# Clock_circuit.net
KiCad netlist of a schematic drawn in Altium Designer
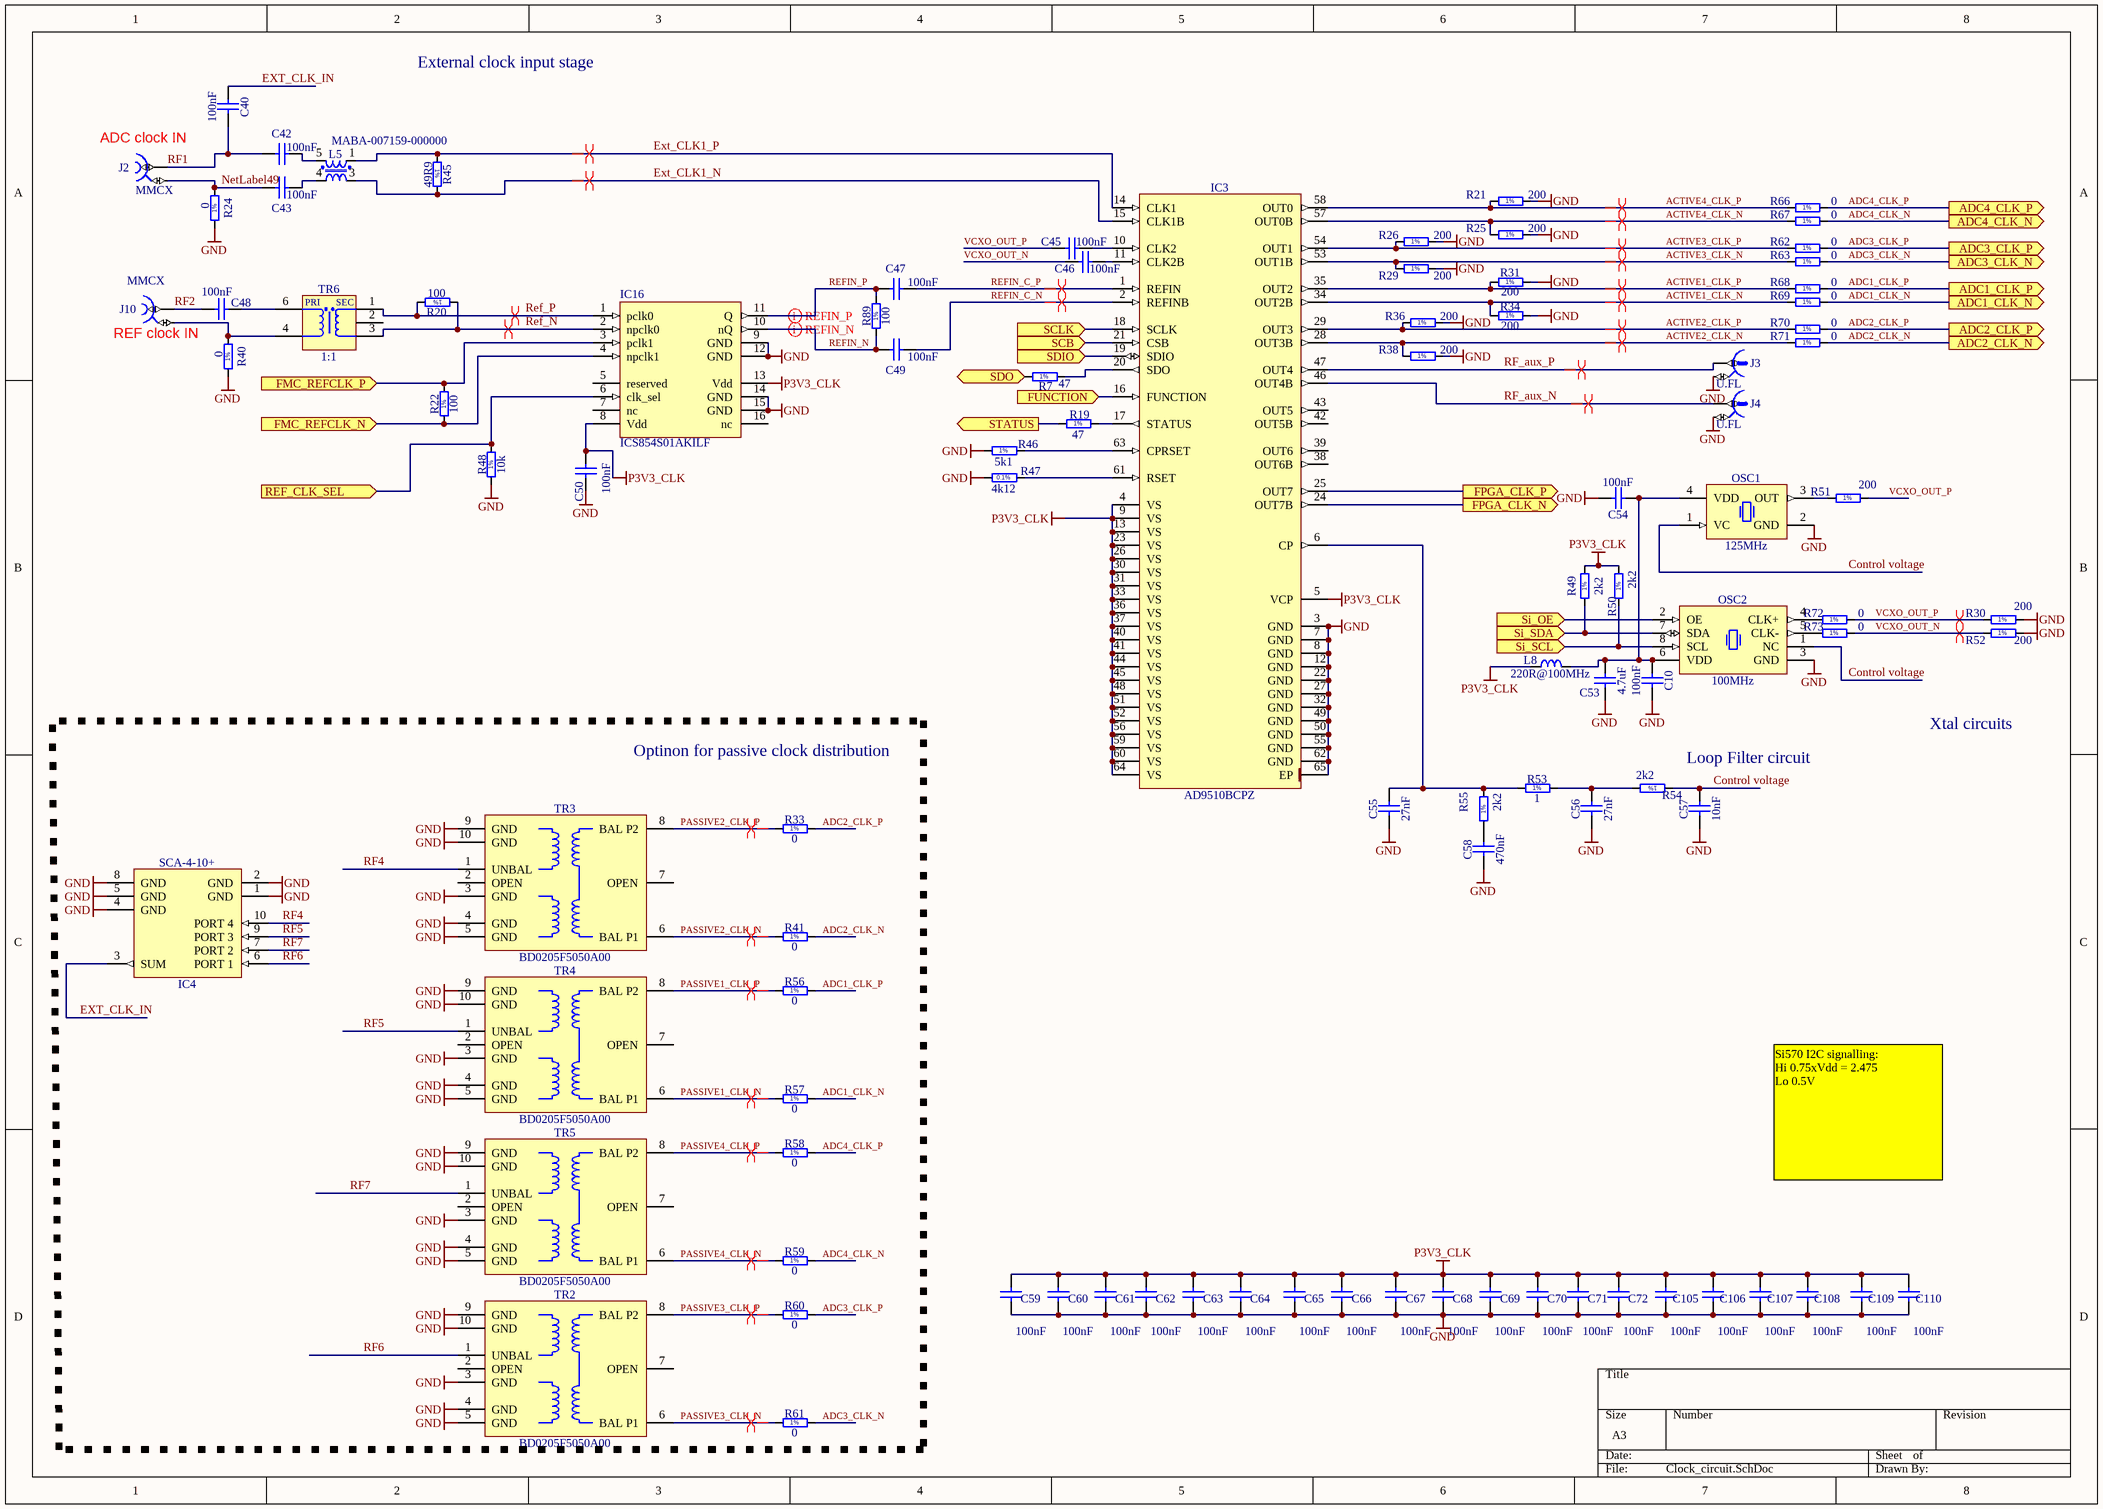
[diagram p0: Clock_circuit.SchDoc]

(export (version "E")
  (design (tool "Eeschema 10.0.6"))
  (components
    (comp (ref "C10")
      (value "100nF")
      (footprint "CAPC0603X33N")
      (description "Non-polarised capacitor")
      (fields
        (field (name "PART NUMBER") "CC0201_100NF_6.3V_10%_X5R")
        (field (name "VOLTAGE") "6.3V")
        (field (name "AUTHOR") "CERN DEM JLC")
      )
      (libsource (lib "Capacitors") (part "Capacitor - non polarized"))
    )
    (comp (ref "C40")
      (value "100nF")
      (footprint "CAPC0603X33N")
      (description "Non-polarised capacitor")
      (fields
        (field (name "PART NUMBER") "CC0201_100NF_6.3V_10%_X5R")
        (field (name "VOLTAGE") "6.3V")
        (field (name "AUTHOR") "CERN DEM JLC")
      )
      (libsource (lib "Capacitors") (part "Capacitor - non polarized"))
    )
    (comp (ref "C42")
      (value "100nF")
      (footprint "CAPC0603X33N")
      (description "Non-polarised capacitor")
      (fields
        (field (name "PART NUMBER") "CC0201_100NF_6.3V_10%_X5R")
        (field (name "VOLTAGE") "6.3V")
        (field (name "AUTHOR") "CERN DEM JLC")
      )
      (libsource (lib "Capacitors") (part "Capacitor - non polarized"))
    )
    (comp (ref "C43")
      (value "100nF")
      (footprint "CAPC0603X33N")
      (description "Non-polarised capacitor")
      (fields
        (field (name "PART NUMBER") "CC0201_100NF_6.3V_10%_X5R")
        (field (name "VOLTAGE") "6.3V")
        (field (name "AUTHOR") "CERN DEM JLC")
      )
      (libsource (lib "Capacitors") (part "Capacitor - non polarized"))
    )
    (comp (ref "C45")
      (value "100nF")
      (footprint "CAPC0603X33N")
      (description "Non-polarised capacitor")
      (fields
        (field (name "PART NUMBER") "CC0201_100NF_6.3V_10%_X5R")
        (field (name "VOLTAGE") "6.3V")
        (field (name "AUTHOR") "CERN DEM JLC")
      )
      (libsource (lib "Capacitors") (part "Capacitor - non polarized"))
    )
    (comp (ref "C46")
      (value "100nF")
      (footprint "CAPC0603X33N")
      (description "Non-polarised capacitor")
      (fields
        (field (name "PART NUMBER") "CC0201_100NF_6.3V_10%_X5R")
        (field (name "VOLTAGE") "6.3V")
        (field (name "AUTHOR") "CERN DEM JLC")
      )
      (libsource (lib "Capacitors") (part "Capacitor - non polarized"))
    )
    (comp (ref "C47")
      (value "100nF")
      (footprint "CAPC0603X33N")
      (description "Non-polarised capacitor")
      (fields
        (field (name "PART NUMBER") "CC0201_100NF_6.3V_10%_X5R")
        (field (name "VOLTAGE") "6.3V")
        (field (name "AUTHOR") "CERN DEM JLC")
      )
      (libsource (lib "Capacitors") (part "Capacitor - non polarized"))
    )
    (comp (ref "C48")
      (value "100nF")
      (footprint "CAPC0603X33N")
      (description "Non-polarised capacitor")
      (fields
        (field (name "PART NUMBER") "CC0201_100NF_6.3V_10%_X5R")
        (field (name "VOLTAGE") "6.3V")
        (field (name "AUTHOR") "CERN DEM JLC")
      )
      (libsource (lib "Capacitors") (part "Capacitor - non polarized"))
    )
    (comp (ref "C49")
      (value "100nF")
      (footprint "CAPC0603X33N")
      (description "Non-polarised capacitor")
      (fields
        (field (name "PART NUMBER") "CC0201_100NF_6.3V_10%_X5R")
        (field (name "VOLTAGE") "6.3V")
        (field (name "AUTHOR") "CERN DEM JLC")
      )
      (libsource (lib "Capacitors") (part "Capacitor - non polarized"))
    )
    (comp (ref "C50")
      (value "100nF")
      (footprint "CAPC0603X33N")
      (description "Non-polarised capacitor")
      (fields
        (field (name "PART NUMBER") "CC0201_100NF_6.3V_10%_X5R")
        (field (name "VOLTAGE") "6.3V")
        (field (name "AUTHOR") "CERN DEM JLC")
      )
      (libsource (lib "Capacitors") (part "Capacitor - non polarized"))
    )
    (comp (ref "C53")
      (value "4.7uF")
      (footprint "CAPC1608X87N")
      (description "Non-polarised capacitor")
      (fields
        (field (name "PART NUMBER") "CC0603_4.7UF_6.3V_10%_X5R")
        (field (name "VOLTAGE") "6.3V")
        (field (name "AUTHOR") "CERN DEM JLC")
      )
      (libsource (lib "Capacitors") (part "Capacitor - non polarized"))
    )
    (comp (ref "C54")
      (value "100nF")
      (footprint "CAPC0603X33N")
      (description "Non-polarised capacitor")
      (fields
        (field (name "PART NUMBER") "CC0201_100NF_6.3V_10%_X5R")
        (field (name "VOLTAGE") "6.3V")
        (field (name "AUTHOR") "CERN DEM JLC")
      )
      (libsource (lib "Capacitors") (part "Capacitor - non polarized"))
    )
    (comp (ref "C55")
      (value "27nF")
      (footprint "CAPC1608X87N")
      (description "Non-polarised capacitor")
      (fields
        (field (name "PART NUMBER") "CC0603_27NF_25V_10%_X7R")
        (field (name "VOLTAGE") "25V")
        (field (name "AUTHOR") "CERN DEM JLC")
      )
      (libsource (lib "Capacitors") (part "Capacitor - non polarized"))
    )
    (comp (ref "C56")
      (value "27nF")
      (footprint "CAPC1608X87N")
      (description "Non-polarised capacitor")
      (fields
        (field (name "PART NUMBER") "CC0603_27NF_25V_10%_X7R")
        (field (name "VOLTAGE") "25V")
        (field (name "AUTHOR") "CERN DEM JLC")
      )
      (libsource (lib "Capacitors") (part "Capacitor - non polarized"))
    )
    (comp (ref "C57")
      (value "10nF")
      (footprint "CAPC1608X87N")
      (description "Non-polarised capacitor")
      (fields
        (field (name "PART NUMBER") "CC0603_10NF_50V_10%_X7R")
        (field (name "VOLTAGE") "50V")
        (field (name "AUTHOR") "CERN DEM JLC")
      )
      (libsource (lib "Capacitors") (part "Capacitor - non polarized"))
    )
    (comp (ref "C58")
      (value "470nF")
      (footprint "CAPC1608X87N")
      (description "Non-polarised capacitor")
      (fields
        (field (name "PART NUMBER") "CC0603_470NF_16V_10%_X5R")
        (field (name "VOLTAGE") "16V")
        (field (name "AUTHOR") "CERN DEM JLC")
      )
      (libsource (lib "Capacitors") (part "Capacitor - non polarized"))
    )
    (comp (ref "C59")
      (value "100nF")
      (footprint "CAPC0603X33N")
      (description "Non-polarised capacitor")
      (fields
        (field (name "PART NUMBER") "CC0201_100NF_6.3V_10%_X5R")
        (field (name "VOLTAGE") "6.3V")
        (field (name "AUTHOR") "CERN DEM JLC")
      )
      (libsource (lib "Capacitors") (part "Capacitor - non polarized"))
    )
    (comp (ref "C60")
      (value "100nF")
      (footprint "CAPC0603X33N")
      (description "Non-polarised capacitor")
      (fields
        (field (name "PART NUMBER") "CC0201_100NF_6.3V_10%_X5R")
        (field (name "VOLTAGE") "6.3V")
        (field (name "AUTHOR") "CERN DEM JLC")
      )
      (libsource (lib "Capacitors") (part "Capacitor - non polarized"))
    )
    (comp (ref "C61")
      (value "100nF")
      (footprint "CAPC0603X33N")
      (description "Non-polarised capacitor")
      (fields
        (field (name "PART NUMBER") "CC0201_100NF_6.3V_10%_X5R")
        (field (name "VOLTAGE") "6.3V")
        (field (name "AUTHOR") "CERN DEM JLC")
      )
      (libsource (lib "Capacitors") (part "Capacitor - non polarized"))
    )
    (comp (ref "C62")
      (value "100nF")
      (footprint "CAPC0603X33N")
      (description "Non-polarised capacitor")
      (fields
        (field (name "PART NUMBER") "CC0201_100NF_6.3V_10%_X5R")
        (field (name "VOLTAGE") "6.3V")
        (field (name "AUTHOR") "CERN DEM JLC")
      )
      (libsource (lib "Capacitors") (part "Capacitor - non polarized"))
    )
    (comp (ref "C63")
      (value "100nF")
      (footprint "CAPC0603X33N")
      (description "Non-polarised capacitor")
      (fields
        (field (name "PART NUMBER") "CC0201_100NF_6.3V_10%_X5R")
        (field (name "VOLTAGE") "6.3V")
        (field (name "AUTHOR") "CERN DEM JLC")
      )
      (libsource (lib "Capacitors") (part "Capacitor - non polarized"))
    )
    (comp (ref "C64")
      (value "100nF")
      (footprint "CAPC0603X33N")
      (description "Non-polarised capacitor")
      (fields
        (field (name "PART NUMBER") "CC0201_100NF_6.3V_10%_X5R")
        (field (name "VOLTAGE") "6.3V")
        (field (name "AUTHOR") "CERN DEM JLC")
      )
      (libsource (lib "Capacitors") (part "Capacitor - non polarized"))
    )
    (comp (ref "C65")
      (value "100nF")
      (footprint "CAPC0603X33N")
      (description "Non-polarised capacitor")
      (fields
        (field (name "PART NUMBER") "CC0201_100NF_6.3V_10%_X5R")
        (field (name "VOLTAGE") "6.3V")
        (field (name "AUTHOR") "CERN DEM JLC")
      )
      (libsource (lib "Capacitors") (part "Capacitor - non polarized"))
    )
    (comp (ref "C66")
      (value "100nF")
      (footprint "CAPC0603X33N")
      (description "Non-polarised capacitor")
      (fields
        (field (name "PART NUMBER") "CC0201_100NF_6.3V_10%_X5R")
        (field (name "VOLTAGE") "6.3V")
        (field (name "AUTHOR") "CERN DEM JLC")
      )
      (libsource (lib "Capacitors") (part "Capacitor - non polarized"))
    )
    (comp (ref "C67")
      (value "100nF")
      (footprint "CAPC0603X33N")
      (description "Non-polarised capacitor")
      (fields
        (field (name "PART NUMBER") "CC0201_100NF_6.3V_10%_X5R")
        (field (name "VOLTAGE") "6.3V")
        (field (name "AUTHOR") "CERN DEM JLC")
      )
      (libsource (lib "Capacitors") (part "Capacitor - non polarized"))
    )
    (comp (ref "C68")
      (value "100nF")
      (footprint "CAPC0603X33N")
      (description "Non-polarised capacitor")
      (fields
        (field (name "PART NUMBER") "CC0201_100NF_6.3V_10%_X5R")
        (field (name "VOLTAGE") "6.3V")
        (field (name "AUTHOR") "CERN DEM JLC")
      )
      (libsource (lib "Capacitors") (part "Capacitor - non polarized"))
    )
    (comp (ref "C69")
      (value "100nF")
      (footprint "CAPC0603X33N")
      (description "Non-polarised capacitor")
      (fields
        (field (name "PART NUMBER") "CC0201_100NF_6.3V_10%_X5R")
        (field (name "VOLTAGE") "6.3V")
        (field (name "AUTHOR") "CERN DEM JLC")
      )
      (libsource (lib "Capacitors") (part "Capacitor - non polarized"))
    )
    (comp (ref "C70")
      (value "100nF")
      (footprint "CAPC0603X33N")
      (description "Non-polarised capacitor")
      (fields
        (field (name "PART NUMBER") "CC0201_100NF_6.3V_10%_X5R")
        (field (name "VOLTAGE") "6.3V")
        (field (name "AUTHOR") "CERN DEM JLC")
      )
      (libsource (lib "Capacitors") (part "Capacitor - non polarized"))
    )
    (comp (ref "C71")
      (value "100nF")
      (footprint "CAPC0603X33N")
      (description "Non-polarised capacitor")
      (fields
        (field (name "PART NUMBER") "CC0201_100NF_6.3V_10%_X5R")
        (field (name "VOLTAGE") "6.3V")
        (field (name "AUTHOR") "CERN DEM JLC")
      )
      (libsource (lib "Capacitors") (part "Capacitor - non polarized"))
    )
    (comp (ref "C72")
      (value "100nF")
      (footprint "CAPC0603X33N")
      (description "Non-polarised capacitor")
      (fields
        (field (name "PART NUMBER") "CC0201_100NF_6.3V_10%_X5R")
        (field (name "VOLTAGE") "6.3V")
        (field (name "AUTHOR") "CERN DEM JLC")
      )
      (libsource (lib "Capacitors") (part "Capacitor - non polarized"))
    )
    (comp (ref "C105")
      (value "100nF")
      (footprint "CAPC0603X33N")
      (description "Non-polarised capacitor")
      (fields
        (field (name "PART NUMBER") "CC0201_100NF_6.3V_10%_X5R")
        (field (name "VOLTAGE") "6.3V")
        (field (name "AUTHOR") "CERN DEM JLC")
      )
      (libsource (lib "Capacitors") (part "Capacitor - non polarized"))
    )
    (comp (ref "C106")
      (value "100nF")
      (footprint "CAPC0603X33N")
      (description "Non-polarised capacitor")
      (fields
        (field (name "PART NUMBER") "CC0201_100NF_6.3V_10%_X5R")
        (field (name "VOLTAGE") "6.3V")
        (field (name "AUTHOR") "CERN DEM JLC")
      )
      (libsource (lib "Capacitors") (part "Capacitor - non polarized"))
    )
    (comp (ref "C107")
      (value "100nF")
      (footprint "CAPC0603X33N")
      (description "Non-polarised capacitor")
      (fields
        (field (name "PART NUMBER") "CC0201_100NF_6.3V_10%_X5R")
        (field (name "VOLTAGE") "6.3V")
        (field (name "AUTHOR") "CERN DEM JLC")
      )
      (libsource (lib "Capacitors") (part "Capacitor - non polarized"))
    )
    (comp (ref "C108")
      (value "100nF")
      (footprint "CAPC0603X33N")
      (description "Non-polarised capacitor")
      (fields
        (field (name "PART NUMBER") "CC0201_100NF_6.3V_10%_X5R")
        (field (name "VOLTAGE") "6.3V")
        (field (name "AUTHOR") "CERN DEM JLC")
      )
      (libsource (lib "Capacitors") (part "Capacitor - non polarized"))
    )
    (comp (ref "C109")
      (value "100nF")
      (footprint "CAPC0603X33N")
      (description "Non-polarised capacitor")
      (fields
        (field (name "PART NUMBER") "CC0201_100NF_6.3V_10%_X5R")
        (field (name "VOLTAGE") "6.3V")
        (field (name "AUTHOR") "CERN DEM JLC")
      )
      (libsource (lib "Capacitors") (part "Capacitor - non polarized"))
    )
    (comp (ref "C110")
      (value "100nF")
      (footprint "CAPC0603X33N")
      (description "Non-polarised capacitor")
      (fields
        (field (name "PART NUMBER") "CC0201_100NF_6.3V_10%_X5R")
        (field (name "VOLTAGE") "6.3V")
        (field (name "AUTHOR") "CERN DEM JLC")
      )
      (libsource (lib "Capacitors") (part "Capacitor - non polarized"))
    )
    (comp (ref "IC3")
      (value "AD9510BCPZ")
      (footprint "QFN50P900X900X100-65N-S485")
      (description "1.2 GHz Clock Distribution IC, PLL Core, Dividers, Delay Adjust, Eight Outputs")
      (fields (field (name "MANUFACTURER") "ANALOG DEVICES") (field (name "AUTHOR") "CERN DEM JLC"))
      (libsource (lib "ICs And Semiconductors") (part "AD9510"))
    )
    (comp (ref "IC4")
      (value "SCA-4-10+")
      (footprint "MINI-CIRCUITS_DZ943")
      (description "4 Way-0° 50 OHM 5 to 1000 MHz Power Splitter/Combiner")
      (fields (field (name "MANUFACTURER") "MINI-CIRCUITS") (field (name "AUTHOR") "CERN DEM JLC"))
      (libsource (lib "ICs And Semiconductors") (part "SCA-4-10+"))
    )
    (comp (ref "IC16")
      (value "ICS854S015CKI-01LF")
      (footprint "QFN127P600-8N")
      (description "2:1 Differential-to-LVDS Multiplexer")
      (fields
        (field (name "MANUFACTURER") "IDT, Integrated Device Technology Inc")
        (field (name "MANUFACTURER PART NUMBER") "ICS854S01AKILF")
      )
      (libsource (lib "ADC_FMC_130_lib") (part "ICS854S015CKI-01LF"))
    )
    (comp (ref "J2")
      (value "Coax_1Female_1Shield")
      (footprint "HUBER-SUHNER_85_MMCX-50-0-1/111 OH")
      (fields
        (field (name "PART NUMBER") "HUBER-SUHNER_85_MMCX-50-0-1/111 OH")
        (field (name "FAMILY") "MMCX")
        (field (name "MANUFACTURER") "HUBER+SUHNER")
        (field (name "MANUFACTURER PART NUMBER") "85_MMCX-50-0-1/111 OH")
        (field (name "AUTHOR") "CERN DEM JLC")
      )
      (libsource (lib "Connectors") (part "Coax_1Female_1Shield"))
    )
    (comp (ref "J3")
      (value "U.FL")
      (footprint "HIROSE_U.FL-R-SMT-1(10)")
      (fields
        (field (name "PART NUMBER") "HIROSE_U.FL-R-SMT-1(10)")
        (field (name "MANUFACTURER") "HIROSE (HRS)")
        (field (name "MANUFACTURER PART NUMBER") "U.FL-R-SMT-1(10)")
        (field (name "AUTHOR") "CERN DEM JLC")
      )
      (libsource (lib "Connectors") (part "Coax_1Male_1Shield"))
    )
    (comp (ref "J4")
      (value "U.FL")
      (footprint "HIROSE_U.FL-R-SMT-1(10)")
      (fields
        (field (name "PART NUMBER") "HIROSE_U.FL-R-SMT-1(10)")
        (field (name "MANUFACTURER") "HIROSE (HRS)")
        (field (name "MANUFACTURER PART NUMBER") "U.FL-R-SMT-1(10)")
        (field (name "AUTHOR") "CERN DEM JLC")
      )
      (libsource (lib "Connectors") (part "Coax_1Male_1Shield"))
    )
    (comp (ref "J10")
      (value "Coax_1Female_1Shield")
      (footprint "HUBER-SUHNER_85_MMCX-50-0-1/111 OH")
      (fields
        (field (name "PART NUMBER") "HUBER-SUHNER_85_MMCX-50-0-1/111 OH")
        (field (name "FAMILY") "MMCX")
        (field (name "MANUFACTURER") "HUBER+SUHNER")
        (field (name "MANUFACTURER PART NUMBER") "85_MMCX-50-0-1/111 OH")
        (field (name "AUTHOR") "CERN DEM JLC")
      )
      (libsource (lib "Connectors") (part "Coax_1Female_1Shield"))
    )
    (comp (ref "L5")
      (value "MABA-007159-000000")
      (footprint "XFMR_MA-COM_SM-22 (H260)")
      (description "MA-COM E-Serie RF 1:1 Transmission Line Ttransformer 4.5-3000MHz")
      (fields
        (field (name "PART NUMBER") "XFMR_MA-COM_MABA-007159-000000")
        (field (name "MANUFACTURER") "MA-COM TECHNOLOGY")
        (field (name "AUTHOR") "CERN DEM JLC")
      )
      (libsource (lib "Inductors & Transformers") (part "XFMR_MA-COM_MABA-007159-000000"))
    )
    (comp (ref "L8")
      (value "220R@100MHz")
      (footprint "INDC1005X55N")
      (description "Inductor")
      (fields
        (field (name "PART NUMBER") "IND0402_MURATA_BLM15HB221SN1")
        (field (name "POWER") "250mA")
        (field (name "AUTHOR") "CERN DEM JLC")
      )
      (libsource (lib "Inductors & Transformers") (part "Inductor"))
    )
    (comp (ref "OSC1")
      (value "125MHz")
      (footprint "OSC_CRYSTEK_CVHD-950")
      (description "Oscillator 4 pins 1=VC 2=GND 3=OUT 4=VDD")
      (fields
        (field (name "PART NUMBER") "OSC_125MHZ_CRYSTEK_CVHD-950-100.000")
        (field (name "MANUFACTURER") "CRYSTEK CRYSTAL")
        (field (name "AUTHOR") "CERN DEM JLC")
      )
      (libsource (lib "ICs And Semiconductors") (part "Oscillator 1VC 2GND 3OUT 4VDD"))
    )
    (comp (ref "OSC2")
      (value "100MHz")
      (footprint "OSC_SILICON-LAB_SI570")
      (description "Any-Rate I2C Programmable XO Oscillator Si570 Serie")
      (fields
        (field (name "PART NUMBER") "OSC_10-280MHZ_SILICON-LAB_Si570BBC000121DG")
        (field (name "MANUFACTURER") "SILICON LABS")
        (field (name "AUTHOR") "CERN DEM JLC")
      )
      (libsource (lib "ICs And Semiconductors") (part "Oscillator SILICON-LAB_Si570"))
    )
    (comp (ref "R7")
      (value "47")
      (footprint "RESC1005X40N")
      (description "Resistor - 1%")
      (fields
        (field (name "PART NUMBER") "R0402_47R_1%_0.0625W_100PPM")
        (field (name "POWER") "0.0625W")
        (field (name "AUTHOR") "CERN DEM JLC")
      )
      (libsource (lib "Resistors") (part "Resistor - 1%"))
    )
    (comp (ref "R19")
      (value "47")
      (footprint "RESC1005X40N")
      (description "Resistor - 1%")
      (fields
        (field (name "PART NUMBER") "R0402_47R_1%_0.0625W_100PPM")
        (field (name "POWER") "0.0625W")
        (field (name "AUTHOR") "CERN DEM JLC")
      )
      (libsource (lib "Resistors") (part "Resistor - 1%"))
    )
    (comp (ref "R20")
      (value "100")
      (footprint "RESC1005X40N")
      (description "Resistor - 1%")
      (fields
        (field (name "PART NUMBER") "R0402_100R_1%_0.0625W_100PPM")
        (field (name "POWER") "0.0625W")
        (field (name "AUTHOR") "CERN DEM JLC")
      )
      (libsource (lib "Resistors") (part "Resistor - 1%"))
    )
    (comp (ref "R21")
      (value "200")
      (footprint "RESC1005X40N")
      (description "Resistor - 1%")
      (fields
        (field (name "PART NUMBER") "R0402_200R_1%_0.0625W_100PPM")
        (field (name "POWER") "0.0625W")
        (field (name "AUTHOR") "CERN DEM JLC")
      )
      (libsource (lib "Resistors") (part "Resistor - 1%"))
    )
    (comp (ref "R22")
      (value "100")
      (footprint "RESC1005X40N")
      (description "Resistor - 1%")
      (fields
        (field (name "PART NUMBER") "R0402_100R_1%_0.0625W_100PPM")
        (field (name "POWER") "0.0625W")
        (field (name "AUTHOR") "CERN DEM JLC")
      )
      (libsource (lib "Resistors") (part "Resistor - 1%"))
    )
    (comp (ref "R24")
      (value "0")
      (footprint "RESC1005X40N")
      (description "Resistor - 1%")
      (fields
        (field (name "PART NUMBER") "R0402_0R_JUMPER")
        (field (name "MANUFACTURER") "GENERIC")
        (field (name "AUTHOR") "CERN DEM JLC")
      )
      (libsource (lib "Resistors") (part "Resistor - 1%"))
    )
    (comp (ref "R25")
      (value "200")
      (footprint "RESC1005X40N")
      (description "Resistor - 1%")
      (fields
        (field (name "PART NUMBER") "R0402_200R_1%_0.0625W_100PPM")
        (field (name "POWER") "0.0625W")
        (field (name "AUTHOR") "CERN DEM JLC")
      )
      (libsource (lib "Resistors") (part "Resistor - 1%"))
    )
    (comp (ref "R26")
      (value "200")
      (footprint "RESC1005X40N")
      (description "Resistor - 1%")
      (fields
        (field (name "PART NUMBER") "R0402_200R_1%_0.0625W_100PPM")
        (field (name "POWER") "0.0625W")
        (field (name "AUTHOR") "CERN DEM JLC")
      )
      (libsource (lib "Resistors") (part "Resistor - 1%"))
    )
    (comp (ref "R29")
      (value "200")
      (footprint "RESC1005X40N")
      (description "Resistor - 1%")
      (fields
        (field (name "PART NUMBER") "R0402_200R_1%_0.0625W_100PPM")
        (field (name "POWER") "0.0625W")
        (field (name "AUTHOR") "CERN DEM JLC")
      )
      (libsource (lib "Resistors") (part "Resistor - 1%"))
    )
    (comp (ref "R30")
      (value "200")
      (footprint "RESC1005X40N")
      (description "Resistor - 1%")
      (fields
        (field (name "PART NUMBER") "R0402_200R_1%_0.0625W_100PPM")
        (field (name "POWER") "0.0625W")
        (field (name "AUTHOR") "CERN DEM JLC")
      )
      (libsource (lib "Resistors") (part "Resistor - 1%"))
    )
    (comp (ref "R31")
      (value "200")
      (footprint "RESC1005X40N")
      (description "Resistor - 1%")
      (fields
        (field (name "PART NUMBER") "R0402_200R_1%_0.0625W_100PPM")
        (field (name "POWER") "0.0625W")
        (field (name "AUTHOR") "CERN DEM JLC")
      )
      (libsource (lib "Resistors") (part "Resistor - 1%"))
    )
    (comp (ref "R33")
      (value "0")
      (footprint "RESC1005X40N")
      (description "Resistor - 1%")
      (fields
        (field (name "PART NUMBER") "R0402_0R_JUMPER")
        (field (name "MANUFACTURER") "GENERIC")
        (field (name "AUTHOR") "CERN DEM JLC")
      )
      (libsource (lib "Resistors") (part "Resistor - 1%"))
    )
    (comp (ref "R34")
      (value "200")
      (footprint "RESC1005X40N")
      (description "Resistor - 1%")
      (fields
        (field (name "PART NUMBER") "R0402_200R_1%_0.0625W_100PPM")
        (field (name "POWER") "0.0625W")
        (field (name "AUTHOR") "CERN DEM JLC")
      )
      (libsource (lib "Resistors") (part "Resistor - 1%"))
    )
    (comp (ref "R36")
      (value "200")
      (footprint "RESC1005X40N")
      (description "Resistor - 1%")
      (fields
        (field (name "PART NUMBER") "R0402_200R_1%_0.0625W_100PPM")
        (field (name "POWER") "0.0625W")
        (field (name "AUTHOR") "CERN DEM JLC")
      )
      (libsource (lib "Resistors") (part "Resistor - 1%"))
    )
    (comp (ref "R38")
      (value "200")
      (footprint "RESC1005X40N")
      (description "Resistor - 1%")
      (fields
        (field (name "PART NUMBER") "R0402_200R_1%_0.0625W_100PPM")
        (field (name "POWER") "0.0625W")
        (field (name "AUTHOR") "CERN DEM JLC")
      )
      (libsource (lib "Resistors") (part "Resistor - 1%"))
    )
    (comp (ref "R40")
      (value "0")
      (footprint "RESC1005X40N")
      (description "Resistor - 1%")
      (fields
        (field (name "PART NUMBER") "R0402_0R_JUMPER")
        (field (name "MANUFACTURER") "GENERIC")
        (field (name "AUTHOR") "CERN DEM JLC")
      )
      (libsource (lib "Resistors") (part "Resistor - 1%"))
    )
    (comp (ref "R41")
      (value "0")
      (footprint "RESC1005X40N")
      (description "Resistor - 1%")
      (fields
        (field (name "PART NUMBER") "R0402_0R_JUMPER")
        (field (name "MANUFACTURER") "GENERIC")
        (field (name "AUTHOR") "CERN DEM JLC")
      )
      (libsource (lib "Resistors") (part "Resistor - 1%"))
    )
    (comp (ref "R45")
      (value "49R9")
      (footprint "RESC1005X40N")
      (description "Resistor - 1%")
      (fields
        (field (name "PART NUMBER") "R0402_49R9_1%_0.0625W_100PPM")
        (field (name "POWER") "0.0625W")
        (field (name "AUTHOR") "CERN DEM JLC")
      )
      (libsource (lib "Resistors") (part "Resistor - 1%"))
    )
    (comp (ref "R46")
      (value "5k1")
      (footprint "RESC1005X40N")
      (description "Resistor - 1%")
      (fields
        (field (name "PART NUMBER") "R0402_5K1_1%_0.0625W_100PPM")
        (field (name "POWER") "0.0625W")
        (field (name "AUTHOR") "CERN DEM JLC")
      )
      (libsource (lib "Resistors") (part "Resistor - 1%"))
    )
    (comp (ref "R47")
      (value "4k12")
      (footprint "RESC1608X55N")
      (description "Resistor - 0.1%")
      (fields
        (field (name "PART NUMBER") "R0603_4K12_0.1%_0.063W_10PPM")
        (field (name "POWER") "0.063W")
        (field (name "AUTHOR") "CERN DEM JLC")
      )
      (libsource (lib "Resistors") (part "Resistor - 0.1%"))
    )
    (comp (ref "R48")
      (value "10k")
      (footprint "RESC1005X40N")
      (description "Resistor - 1%")
      (fields
        (field (name "PART NUMBER") "R0402_10K_1%_0.0625W_100PPM")
        (field (name "POWER") "0.0625W")
        (field (name "AUTHOR") "CERN DEM JLC")
      )
      (libsource (lib "Resistors") (part "Resistor - 1%"))
    )
    (comp (ref "R49")
      (value "2k2")
      (footprint "RESC1005X40N")
      (description "Resistor - 1%")
      (fields
        (field (name "PART NUMBER") "R0402_2K2_1%_0.0625W_100PPM")
        (field (name "POWER") "0.0625W")
        (field (name "AUTHOR") "CERN DEM JLC")
      )
      (libsource (lib "Resistors") (part "Resistor - 1%"))
    )
    (comp (ref "R50")
      (value "2k2")
      (footprint "RESC1005X40N")
      (description "Resistor - 1%")
      (fields
        (field (name "PART NUMBER") "R0402_2K2_1%_0.0625W_100PPM")
        (field (name "POWER") "0.0625W")
        (field (name "AUTHOR") "CERN DEM JLC")
      )
      (libsource (lib "Resistors") (part "Resistor - 1%"))
    )
    (comp (ref "R51")
      (value "200")
      (footprint "RESC1005X40N")
      (description "Resistor - 1%")
      (fields
        (field (name "PART NUMBER") "R0402_200R_1%_0.0625W_100PPM")
        (field (name "POWER") "0.0625W")
        (field (name "AUTHOR") "CERN DEM JLC")
      )
      (libsource (lib "Resistors") (part "Resistor - 1%"))
    )
    (comp (ref "R52")
      (value "200")
      (footprint "RESC1005X40N")
      (description "Resistor - 1%")
      (fields
        (field (name "PART NUMBER") "R0402_200R_1%_0.0625W_100PPM")
        (field (name "POWER") "0.0625W")
        (field (name "AUTHOR") "CERN DEM JLC")
      )
      (libsource (lib "Resistors") (part "Resistor - 1%"))
    )
    (comp (ref "R53")
      (value "1")
      (footprint "RESC1005X40N")
      (description "Resistor - 1%")
      (fields
        (field (name "PART NUMBER") "R0402_1R_1%_0.0625W_200PPM")
        (field (name "POWER") "0.0625W")
        (field (name "AUTHOR") "CERN DEM JLC")
      )
      (libsource (lib "Resistors") (part "Resistor - 1%"))
    )
    (comp (ref "R54")
      (value "2k2")
      (footprint "RESC1005X40N")
      (description "Resistor - 1%")
      (fields
        (field (name "PART NUMBER") "R0402_2K2_1%_0.0625W_100PPM")
        (field (name "POWER") "0.0625W")
        (field (name "AUTHOR") "CERN DEM JLC")
      )
      (libsource (lib "Resistors") (part "Resistor - 1%"))
    )
    (comp (ref "R55")
      (value "2k2")
      (footprint "RESC1005X40N")
      (description "Resistor - 1%")
      (fields
        (field (name "PART NUMBER") "R0402_2K2_1%_0.0625W_100PPM")
        (field (name "POWER") "0.0625W")
        (field (name "AUTHOR") "CERN DEM JLC")
      )
      (libsource (lib "Resistors") (part "Resistor - 1%"))
    )
    (comp (ref "R56")
      (value "0")
      (footprint "RESC1005X40N")
      (description "Resistor - 1%")
      (fields
        (field (name "PART NUMBER") "R0402_0R_JUMPER")
        (field (name "MANUFACTURER") "GENERIC")
        (field (name "AUTHOR") "CERN DEM JLC")
      )
      (libsource (lib "Resistors") (part "Resistor - 1%"))
    )
    (comp (ref "R57")
      (value "0")
      (footprint "RESC1005X40N")
      (description "Resistor - 1%")
      (fields
        (field (name "PART NUMBER") "R0402_0R_JUMPER")
        (field (name "MANUFACTURER") "GENERIC")
        (field (name "AUTHOR") "CERN DEM JLC")
      )
      (libsource (lib "Resistors") (part "Resistor - 1%"))
    )
    (comp (ref "R58")
      (value "0")
      (footprint "RESC1005X40N")
      (description "Resistor - 1%")
      (fields
        (field (name "PART NUMBER") "R0402_0R_JUMPER")
        (field (name "MANUFACTURER") "GENERIC")
        (field (name "AUTHOR") "CERN DEM JLC")
      )
      (libsource (lib "Resistors") (part "Resistor - 1%"))
    )
    (comp (ref "R59")
      (value "0")
      (footprint "RESC1005X40N")
      (description "Resistor - 1%")
      (fields
        (field (name "PART NUMBER") "R0402_0R_JUMPER")
        (field (name "MANUFACTURER") "GENERIC")
        (field (name "AUTHOR") "CERN DEM JLC")
      )
      (libsource (lib "Resistors") (part "Resistor - 1%"))
    )
    (comp (ref "R60")
      (value "0")
      (footprint "RESC1005X40N")
      (description "Resistor - 1%")
      (fields
        (field (name "PART NUMBER") "R0402_0R_JUMPER")
        (field (name "MANUFACTURER") "GENERIC")
        (field (name "AUTHOR") "CERN DEM JLC")
      )
      (libsource (lib "Resistors") (part "Resistor - 1%"))
    )
    (comp (ref "R61")
      (value "0")
      (footprint "RESC1005X40N")
      (description "Resistor - 1%")
      (fields
        (field (name "PART NUMBER") "R0402_0R_JUMPER")
        (field (name "MANUFACTURER") "GENERIC")
        (field (name "AUTHOR") "CERN DEM JLC")
      )
      (libsource (lib "Resistors") (part "Resistor - 1%"))
    )
    (comp (ref "R62")
      (value "0")
      (footprint "RESC1005X40N")
      (description "Resistor - 1%")
      (fields
        (field (name "PART NUMBER") "R0402_0R_JUMPER")
        (field (name "MANUFACTURER") "GENERIC")
        (field (name "AUTHOR") "CERN DEM JLC")
      )
      (libsource (lib "Resistors") (part "Resistor - 1%"))
    )
    (comp (ref "R63")
      (value "0")
      (footprint "RESC1005X40N")
      (description "Resistor - 1%")
      (fields
        (field (name "PART NUMBER") "R0402_0R_JUMPER")
        (field (name "MANUFACTURER") "GENERIC")
        (field (name "AUTHOR") "CERN DEM JLC")
      )
      (libsource (lib "Resistors") (part "Resistor - 1%"))
    )
    (comp (ref "R66")
      (value "0")
      (footprint "RESC1005X40N")
      (description "Resistor - 1%")
      (fields
        (field (name "PART NUMBER") "R0402_0R_JUMPER")
        (field (name "MANUFACTURER") "GENERIC")
        (field (name "AUTHOR") "CERN DEM JLC")
      )
      (libsource (lib "Resistors") (part "Resistor - 1%"))
    )
    (comp (ref "R67")
      (value "0")
      (footprint "RESC1005X40N")
      (description "Resistor - 1%")
      (fields
        (field (name "PART NUMBER") "R0402_0R_JUMPER")
        (field (name "MANUFACTURER") "GENERIC")
        (field (name "AUTHOR") "CERN DEM JLC")
      )
      (libsource (lib "Resistors") (part "Resistor - 1%"))
    )
    (comp (ref "R68")
      (value "0")
      (footprint "RESC1005X40N")
      (description "Resistor - 1%")
      (fields
        (field (name "PART NUMBER") "R0402_0R_JUMPER")
        (field (name "MANUFACTURER") "GENERIC")
        (field (name "AUTHOR") "CERN DEM JLC")
      )
      (libsource (lib "Resistors") (part "Resistor - 1%"))
    )
    (comp (ref "R69")
      (value "0")
      (footprint "RESC1005X40N")
      (description "Resistor - 1%")
      (fields
        (field (name "PART NUMBER") "R0402_0R_JUMPER")
        (field (name "MANUFACTURER") "GENERIC")
        (field (name "AUTHOR") "CERN DEM JLC")
      )
      (libsource (lib "Resistors") (part "Resistor - 1%"))
    )
    (comp (ref "R70")
      (value "0")
      (footprint "RESC1005X40N")
      (description "Resistor - 1%")
      (fields
        (field (name "PART NUMBER") "R0402_0R_JUMPER")
        (field (name "MANUFACTURER") "GENERIC")
        (field (name "AUTHOR") "CERN DEM JLC")
      )
      (libsource (lib "Resistors") (part "Resistor - 1%"))
    )
    (comp (ref "R71")
      (value "0")
      (footprint "RESC1005X40N")
      (description "Resistor - 1%")
      (fields
        (field (name "PART NUMBER") "R0402_0R_JUMPER")
        (field (name "MANUFACTURER") "GENERIC")
        (field (name "AUTHOR") "CERN DEM JLC")
      )
      (libsource (lib "Resistors") (part "Resistor - 1%"))
    )
    (comp (ref "R72")
      (value "0")
      (footprint "RESC1005X40N")
      (description "Resistor - 1%")
      (fields
        (field (name "PART NUMBER") "R0402_0R_JUMPER")
        (field (name "MANUFACTURER") "GENERIC")
        (field (name "AUTHOR") "CERN DEM JLC")
      )
      (libsource (lib "Resistors") (part "Resistor - 1%"))
    )
    (comp (ref "R73")
      (value "0")
      (footprint "RESC1005X40N")
      (description "Resistor - 1%")
      (fields
        (field (name "PART NUMBER") "R0402_0R_JUMPER")
        (field (name "MANUFACTURER") "GENERIC")
        (field (name "AUTHOR") "CERN DEM JLC")
      )
      (libsource (lib "Resistors") (part "Resistor - 1%"))
    )
    (comp (ref "R89")
      (value "100")
      (footprint "RESC1005X40N")
      (description "Resistor - 1%")
      (fields
        (field (name "PART NUMBER") "R0402_100R_1%_0.0625W_100PPM")
        (field (name "POWER") "0.0625W")
        (field (name "AUTHOR") "CERN DEM JLC")
      )
      (libsource (lib "Resistors") (part "Resistor - 1%"))
    )
    (comp (ref "TR2")
      (value "BD0205F5050A00")
      (footprint "XFMR_ANAREN_BD0205F5050A00")
      (description "70MHz - 1000MHz Ultra Low Profile Sub-Miniature Balanced to Unbalanced Transformer")
      (fields
        (field (name "PART NUMBER") "XFMR_ANAREN_BD0205F5050A00")
        (field (name "MANUFACTURER") "ANAREN")
        (field (name "AUTHOR") "CERN DEM JLC")
      )
      (libsource (lib "Inductors & Transformers") (part "XFMR_ANAREN_BD0205F5050A00"))
    )
    (comp (ref "TR3")
      (value "BD0205F5050A00")
      (footprint "XFMR_ANAREN_BD0205F5050A00")
      (description "70MHz - 1000MHz Ultra Low Profile Sub-Miniature Balanced to Unbalanced Transformer")
      (fields
        (field (name "PART NUMBER") "XFMR_ANAREN_BD0205F5050A00")
        (field (name "MANUFACTURER") "ANAREN")
        (field (name "AUTHOR") "CERN DEM JLC")
      )
      (libsource (lib "Inductors & Transformers") (part "XFMR_ANAREN_BD0205F5050A00"))
    )
    (comp (ref "TR4")
      (value "BD0205F5050A00")
      (footprint "XFMR_ANAREN_BD0205F5050A00")
      (description "70MHz - 1000MHz Ultra Low Profile Sub-Miniature Balanced to Unbalanced Transformer")
      (fields
        (field (name "PART NUMBER") "XFMR_ANAREN_BD0205F5050A00")
        (field (name "MANUFACTURER") "ANAREN")
        (field (name "AUTHOR") "CERN DEM JLC")
      )
      (libsource (lib "Inductors & Transformers") (part "XFMR_ANAREN_BD0205F5050A00"))
    )
    (comp (ref "TR5")
      (value "BD0205F5050A00")
      (footprint "XFMR_ANAREN_BD0205F5050A00")
      (description "70MHz - 1000MHz Ultra Low Profile Sub-Miniature Balanced to Unbalanced Transformer")
      (fields
        (field (name "PART NUMBER") "XFMR_ANAREN_BD0205F5050A00")
        (field (name "MANUFACTURER") "ANAREN")
        (field (name "AUTHOR") "CERN DEM JLC")
      )
      (libsource (lib "Inductors & Transformers") (part "XFMR_ANAREN_BD0205F5050A00"))
    )
    (comp (ref "TR6")
      (value "1:1")
      (footprint "XFMR_MINI-CIRCUITS_AT224-1")
      (description "50 Ohm  0.4 To 500MHz RF Transformers")
      (fields
        (field (name "PART NUMBER") "XFMR_MINI-CIRCUITS_TC1-1T+")
        (field (name "MANUFACTURER") "MINI-CIRCUITS")
        (field (name "AUTHOR") "CERN DEM JLC")
      )
      (libsource (lib "Inductors & Transformers") (part "XFMR_MINI-CIRCUITS_TC1-1+"))
    )
  )
  (nets
    (net (code "1") (name "/ACTIVE1_CLK_N") (class "Default")
      (node (ref "IC3") (pin "34") (pinfunction "OUT2B_34") (pintype "output"))
      (node (ref "R34") (pin "1") (pinfunction "1_1") (pintype "passive"))
      (node (ref "R69") (pin "1") (pinfunction "1_1") (pintype "passive"))
    )
    (net (code "2") (name "/ACTIVE1_CLK_P") (class "Default")
      (node (ref "IC3") (pin "35") (pinfunction "OUT2_35") (pintype "output"))
      (node (ref "R31") (pin "1") (pinfunction "1_1") (pintype "passive"))
      (node (ref "R68") (pin "1") (pinfunction "1_1") (pintype "passive"))
    )
    (net (code "3") (name "/ACTIVE2_CLK_N") (class "Default")
      (node (ref "IC3") (pin "28") (pinfunction "OUT3B_28") (pintype "output"))
      (node (ref "R38") (pin "1") (pinfunction "1_1") (pintype "passive"))
      (node (ref "R71") (pin "1") (pinfunction "1_1") (pintype "passive"))
    )
    (net (code "4") (name "/ACTIVE2_CLK_P") (class "Default")
      (node (ref "IC3") (pin "29") (pinfunction "OUT3_29") (pintype "output"))
      (node (ref "R36") (pin "1") (pinfunction "1_1") (pintype "passive"))
      (node (ref "R70") (pin "1") (pinfunction "1_1") (pintype "passive"))
    )
    (net (code "5") (name "/ACTIVE3_CLK_N") (class "Default")
      (node (ref "IC3") (pin "53") (pinfunction "OUT1B_53") (pintype "output"))
      (node (ref "R29") (pin "1") (pinfunction "1_1") (pintype "passive"))
      (node (ref "R63") (pin "1") (pinfunction "1_1") (pintype "passive"))
    )
    (net (code "6") (name "/ACTIVE3_CLK_P") (class "Default")
      (node (ref "IC3") (pin "54") (pinfunction "OUT1_54") (pintype "output"))
      (node (ref "R26") (pin "1") (pinfunction "1_1") (pintype "passive"))
      (node (ref "R62") (pin "1") (pinfunction "1_1") (pintype "passive"))
    )
    (net (code "7") (name "/ACTIVE4_CLK_N") (class "Default")
      (node (ref "IC3") (pin "57") (pinfunction "OUT0B_57") (pintype "output"))
      (node (ref "R25") (pin "1") (pinfunction "1_1") (pintype "passive"))
      (node (ref "R67") (pin "1") (pinfunction "1_1") (pintype "passive"))
    )
    (net (code "8") (name "/ACTIVE4_CLK_P") (class "Default")
      (node (ref "IC3") (pin "58") (pinfunction "OUT0_58") (pintype "output"))
      (node (ref "R21") (pin "1") (pinfunction "1_1") (pintype "passive"))
      (node (ref "R66") (pin "1") (pinfunction "1_1") (pintype "passive"))
    )
    (net (code "9") (name "/ADC1_CLK_N") (class "Default")
      (node (ref "R57") (pin "2") (pinfunction "2_2") (pintype "passive"))
      (node (ref "R69") (pin "2") (pinfunction "2_2") (pintype "passive"))
    )
    (net (code "10") (name "/ADC1_CLK_P") (class "Default")
      (node (ref "R56") (pin "2") (pinfunction "2_2") (pintype "passive"))
      (node (ref "R68") (pin "2") (pinfunction "2_2") (pintype "passive"))
    )
    (net (code "11") (name "/ADC2_CLK_N") (class "Default")
      (node (ref "R41") (pin "2") (pinfunction "2_2") (pintype "passive"))
      (node (ref "R71") (pin "2") (pinfunction "2_2") (pintype "passive"))
    )
    (net (code "12") (name "/ADC2_CLK_P") (class "Default")
      (node (ref "R33") (pin "2") (pinfunction "2_2") (pintype "passive"))
      (node (ref "R70") (pin "2") (pinfunction "2_2") (pintype "passive"))
    )
    (net (code "13") (name "/ADC3_CLK_N") (class "Default")
      (node (ref "R61") (pin "2") (pinfunction "2_2") (pintype "passive"))
      (node (ref "R63") (pin "2") (pinfunction "2_2") (pintype "passive"))
    )
    (net (code "14") (name "/ADC3_CLK_P") (class "Default")
      (node (ref "R60") (pin "2") (pinfunction "2_2") (pintype "passive"))
      (node (ref "R62") (pin "2") (pinfunction "2_2") (pintype "passive"))
    )
    (net (code "15") (name "/ADC4_CLK_N") (class "Default")
      (node (ref "R59") (pin "2") (pinfunction "2_2") (pintype "passive"))
      (node (ref "R67") (pin "2") (pinfunction "2_2") (pintype "passive"))
    )
    (net (code "16") (name "/ADC4_CLK_P") (class "Default")
      (node (ref "R58") (pin "2") (pinfunction "2_2") (pintype "passive"))
      (node (ref "R66") (pin "2") (pinfunction "2_2") (pintype "passive"))
    )
    (net (code "17") (name "/Control voltage") (class "Default")
      (node (ref "C57") (pin "2") (pinfunction "2_2") (pintype "passive"))
      (node (ref "OSC1") (pin "1") (pinfunction "VC_1") (pintype "input"))
      (node (ref "OSC2") (pin "1") (pinfunction "NC_1") (pintype "passive"))
      (node (ref "R54") (pin "1") (pinfunction "1_1") (pintype "passive"))
    )
    (net (code "18") (name "/EXT_CLK_IN") (class "Default")
      (node (ref "C40") (pin "1") (pinfunction "1_1") (pintype "passive"))
      (node (ref "IC4") (pin "3") (pinfunction "SUM_3") (pintype "output"))
    )
    (net (code "19") (name "/Ext_CLK1_N") (class "Default")
      (node (ref "IC3") (pin "15") (pinfunction "CLK1B_15") (pintype "input"))
      (node (ref "L5") (pin "3") (pinfunction "3_3") (pintype "passive"))
      (node (ref "R45") (pin "2") (pinfunction "2_2") (pintype "passive"))
    )
    (net (code "20") (name "/Ext_CLK1_P") (class "Default")
      (node (ref "IC3") (pin "14") (pinfunction "CLK1_14") (pintype "input"))
      (node (ref "L5") (pin "1") (pinfunction "1_1") (pintype "passive"))
      (node (ref "R45") (pin "1") (pinfunction "1_1") (pintype "passive"))
    )
    (net (code "21") (name "/FMC_REFCLK_N") (class "Default")
      (node (ref "IC16") (pin "4") (pinfunction "npclk1_4") (pintype "input"))
      (node (ref "R22") (pin "1") (pinfunction "1_1") (pintype "passive"))
    )
    (net (code "22") (name "/FMC_REFCLK_P") (class "Default")
      (node (ref "IC16") (pin "3") (pinfunction "pclk1_3") (pintype "input"))
      (node (ref "R22") (pin "2") (pinfunction "2_2") (pintype "passive"))
    )
    (net (code "23") (name "/FPGA_CLK_N") (class "Default")
      (node (ref "IC3") (pin "24") (pinfunction "OUT7B_24") (pintype "output"))
    )
    (net (code "24") (name "/FPGA_CLK_P") (class "Default")
      (node (ref "IC3") (pin "25") (pinfunction "OUT7_25") (pintype "output"))
    )
    (net (code "25") (name "/FUNCTION") (class "Default")
      (node (ref "IC3") (pin "16") (pinfunction "FUNCTION_16") (pintype "input"))
    )
    (net (code "26") (name "/NetLabel49") (class "Default")
      (node (ref "C43") (pin "2") (pinfunction "2_2") (pintype "passive"))
      (node (ref "J2") (pin "2") (pinfunction "2_2") (pintype "bidirectional"))
      (node (ref "R24") (pin "2") (pinfunction "2_2") (pintype "passive"))
    )
    (net (code "27") (name "/PASSIVE1_CLK_N") (class "Default")
      (node (ref "R57") (pin "1") (pinfunction "1_1") (pintype "passive"))
      (node (ref "TR4") (pin "6") (pinfunction "BAL_P1_6") (pintype "passive"))
    )
    (net (code "28") (name "/PASSIVE1_CLK_P") (class "Default")
      (node (ref "R56") (pin "1") (pinfunction "1_1") (pintype "passive"))
      (node (ref "TR4") (pin "8") (pinfunction "BAL_P2_8") (pintype "passive"))
    )
    (net (code "29") (name "/PASSIVE2_CLK_N") (class "Default")
      (node (ref "R41") (pin "1") (pinfunction "1_1") (pintype "passive"))
      (node (ref "TR3") (pin "6") (pinfunction "BAL_P1_6") (pintype "passive"))
    )
    (net (code "30") (name "/PASSIVE2_CLK_P") (class "Default")
      (node (ref "R33") (pin "1") (pinfunction "1_1") (pintype "passive"))
      (node (ref "TR3") (pin "8") (pinfunction "BAL_P2_8") (pintype "passive"))
    )
    (net (code "31") (name "/PASSIVE3_CLK_N") (class "Default")
      (node (ref "R61") (pin "1") (pinfunction "1_1") (pintype "passive"))
      (node (ref "TR2") (pin "6") (pinfunction "BAL_P1_6") (pintype "passive"))
    )
    (net (code "32") (name "/PASSIVE3_CLK_P") (class "Default")
      (node (ref "R60") (pin "1") (pinfunction "1_1") (pintype "passive"))
      (node (ref "TR2") (pin "8") (pinfunction "BAL_P2_8") (pintype "passive"))
    )
    (net (code "33") (name "/PASSIVE4_CLK_N") (class "Default")
      (node (ref "R59") (pin "1") (pinfunction "1_1") (pintype "passive"))
      (node (ref "TR5") (pin "6") (pinfunction "BAL_P1_6") (pintype "passive"))
    )
    (net (code "34") (name "/PASSIVE4_CLK_P") (class "Default")
      (node (ref "R58") (pin "1") (pinfunction "1_1") (pintype "passive"))
      (node (ref "TR5") (pin "8") (pinfunction "BAL_P2_8") (pintype "passive"))
    )
    (net (code "35") (name "/REFIN_C_N") (class "Default")
      (node (ref "C49") (pin "1") (pinfunction "1_1") (pintype "passive"))
      (node (ref "IC3") (pin "2") (pinfunction "REFINB_2") (pintype "input"))
    )
    (net (code "36") (name "/REFIN_C_P") (class "Default")
      (node (ref "C47") (pin "1") (pinfunction "1_1") (pintype "passive"))
      (node (ref "IC3") (pin "1") (pinfunction "REFIN_1") (pintype "input"))
    )
    (net (code "37") (name "/REFIN_N") (class "Default")
      (node (ref "C49") (pin "2") (pinfunction "2_2") (pintype "passive"))
      (node (ref "IC16") (pin "10") (pinfunction "nQ_10") (pintype "output"))
      (node (ref "R89") (pin "1") (pinfunction "1_1") (pintype "passive"))
    )
    (net (code "38") (name "/REFIN_P") (class "Default")
      (node (ref "C47") (pin "2") (pinfunction "2_2") (pintype "passive"))
      (node (ref "IC16") (pin "11") (pinfunction "Q_11") (pintype "output"))
      (node (ref "R89") (pin "2") (pinfunction "2_2") (pintype "passive"))
    )
    (net (code "39") (name "/REF_CLK_SEL") (class "Default")
      (node (ref "IC16") (pin "6") (pinfunction "clk_sel_6") (pintype "input"))
      (node (ref "R48") (pin "2") (pinfunction "2_2") (pintype "passive"))
    )
    (net (code "40") (name "/RF1") (class "Default")
      (node (ref "C40") (pin "2") (pinfunction "2_2") (pintype "passive"))
      (node (ref "C42") (pin "2") (pinfunction "2_2") (pintype "passive"))
      (node (ref "J2") (pin "1") (pinfunction "1_1") (pintype "bidirectional"))
    )
    (net (code "41") (name "/RF2") (class "Default")
      (node (ref "C48") (pin "2") (pinfunction "2_2") (pintype "passive"))
      (node (ref "J10") (pin "1") (pinfunction "1_1") (pintype "bidirectional"))
    )
    (net (code "42") (name "/RF4") (class "Default")
      (node (ref "IC4") (pin "10") (pinfunction "PORT_4_10") (pintype "input"))
      (node (ref "TR3") (pin "1") (pinfunction "UNBAL_1") (pintype "passive"))
    )
    (net (code "43") (name "/RF5") (class "Default")
      (node (ref "IC4") (pin "9") (pinfunction "PORT_3_9") (pintype "input"))
      (node (ref "TR4") (pin "1") (pinfunction "UNBAL_1") (pintype "passive"))
    )
    (net (code "44") (name "/RF6") (class "Default")
      (node (ref "IC4") (pin "6") (pinfunction "PORT_1_6") (pintype "input"))
      (node (ref "TR2") (pin "1") (pinfunction "UNBAL_1") (pintype "passive"))
    )
    (net (code "45") (name "/RF7") (class "Default")
      (node (ref "IC4") (pin "7") (pinfunction "PORT_2_7") (pintype "input"))
      (node (ref "TR5") (pin "1") (pinfunction "UNBAL_1") (pintype "passive"))
    )
    (net (code "46") (name "/RF_aux_N") (class "Default")
      (node (ref "IC3") (pin "46") (pinfunction "OUT4B_46") (pintype "output"))
      (node (ref "J4") (pin "1") (pinfunction "1_1") (pintype "bidirectional"))
    )
    (net (code "47") (name "/RF_aux_P") (class "Default")
      (node (ref "IC3") (pin "47") (pinfunction "OUT4_47") (pintype "output"))
      (node (ref "J3") (pin "1") (pinfunction "1_1") (pintype "bidirectional"))
    )
    (net (code "48") (name "/Ref_N") (class "Default")
      (node (ref "IC16") (pin "2") (pinfunction "npclk0_2") (pintype "input"))
      (node (ref "R20") (pin "1") (pinfunction "1_1") (pintype "passive"))
      (node (ref "TR6") (pin "3") (pinfunction "S_3") (pintype "passive"))
    )
    (net (code "49") (name "/Ref_P") (class "Default")
      (node (ref "IC16") (pin "1") (pinfunction "pclk0_1") (pintype "input"))
      (node (ref "R20") (pin "2") (pinfunction "2_2") (pintype "passive"))
      (node (ref "TR6") (pin "1") (pinfunction "SDOT_1") (pintype "passive"))
    )
    (net (code "50") (name "/SCB") (class "Default")
      (node (ref "IC3") (pin "21") (pinfunction "CSB_21") (pintype "input"))
    )
    (net (code "51") (name "/SCLK") (class "Default")
      (node (ref "IC3") (pin "18") (pinfunction "SCLK_18") (pintype "input"))
    )
    (net (code "52") (name "/SDIO") (class "Default")
      (node (ref "IC3") (pin "19") (pinfunction "SDIO_19") (pintype "bidirectional"))
    )
    (net (code "53") (name "/SDO") (class "Default")
      (node (ref "R7") (pin "1") (pinfunction "1_1") (pintype "passive"))
    )
    (net (code "54") (name "/STATUS") (class "Default")
      (node (ref "R19") (pin "1") (pinfunction "1_1") (pintype "passive"))
    )
    (net (code "55") (name "/Si_OE") (class "Default")
      (node (ref "OSC2") (pin "2") (pinfunction "OE_2") (pintype "input"))
    )
    (net (code "56") (name "/Si_SCL") (class "Default")
      (node (ref "OSC2") (pin "8") (pinfunction "SCL_8") (pintype "input"))
      (node (ref "R50") (pin "1") (pinfunction "1_1") (pintype "passive"))
    )
    (net (code "57") (name "/Si_SDA") (class "Default")
      (node (ref "OSC2") (pin "7") (pinfunction "SDA_7") (pintype "bidirectional"))
      (node (ref "R49") (pin "1") (pinfunction "1_1") (pintype "passive"))
    )
    (net (code "58") (name "/VCXO_OUT_N") (class "Default")
      (node (ref "C46") (pin "2") (pinfunction "2_2") (pintype "passive"))
      (node (ref "R52") (pin "1") (pinfunction "1_1") (pintype "passive"))
      (node (ref "R73") (pin "2") (pinfunction "2_2") (pintype "passive"))
    )
    (net (code "59") (name "/VCXO_OUT_P") (class "Default")
      (node (ref "C45") (pin "2") (pinfunction "2_2") (pintype "passive"))
      (node (ref "R30") (pin "1") (pinfunction "1_1") (pintype "passive"))
      (node (ref "R51") (pin "2") (pinfunction "2_2") (pintype "passive"))
      (node (ref "R72") (pin "2") (pinfunction "2_2") (pintype "passive"))
    )
    (net (code "60") (name "GND") (class "Default")
      (node (ref "C10") (pin "2") (pinfunction "2_2") (pintype "passive"))
      (node (ref "C105") (pin "1") (pinfunction "1_1") (pintype "passive"))
      (node (ref "C106") (pin "1") (pinfunction "1_1") (pintype "passive"))
      (node (ref "C107") (pin "1") (pinfunction "1_1") (pintype "passive"))
      (node (ref "C108") (pin "1") (pinfunction "1_1") (pintype "passive"))
      (node (ref "C109") (pin "1") (pinfunction "1_1") (pintype "passive"))
      (node (ref "C110") (pin "1") (pinfunction "1_1") (pintype "passive"))
      (node (ref "C50") (pin "2") (pinfunction "2_2") (pintype "passive"))
      (node (ref "C53") (pin "1") (pinfunction "1_1") (pintype "passive"))
      (node (ref "C54") (pin "2") (pinfunction "2_2") (pintype "passive"))
      (node (ref "C55") (pin "1") (pinfunction "1_1") (pintype "passive"))
      (node (ref "C56") (pin "1") (pinfunction "1_1") (pintype "passive"))
      (node (ref "C57") (pin "1") (pinfunction "1_1") (pintype "passive"))
      (node (ref "C58") (pin "1") (pinfunction "1_1") (pintype "passive"))
      (node (ref "C59") (pin "1") (pinfunction "1_1") (pintype "passive"))
      (node (ref "C60") (pin "1") (pinfunction "1_1") (pintype "passive"))
      (node (ref "C61") (pin "1") (pinfunction "1_1") (pintype "passive"))
      (node (ref "C62") (pin "1") (pinfunction "1_1") (pintype "passive"))
      (node (ref "C63") (pin "1") (pinfunction "1_1") (pintype "passive"))
      (node (ref "C64") (pin "1") (pinfunction "1_1") (pintype "passive"))
      (node (ref "C65") (pin "1") (pinfunction "1_1") (pintype "passive"))
      (node (ref "C66") (pin "1") (pinfunction "1_1") (pintype "passive"))
      (node (ref "C67") (pin "1") (pinfunction "1_1") (pintype "passive"))
      (node (ref "C68") (pin "1") (pinfunction "1_1") (pintype "passive"))
      (node (ref "C69") (pin "1") (pinfunction "1_1") (pintype "passive"))
      (node (ref "C70") (pin "1") (pinfunction "1_1") (pintype "passive"))
      (node (ref "C71") (pin "1") (pinfunction "1_1") (pintype "passive"))
      (node (ref "C72") (pin "1") (pinfunction "1_1") (pintype "passive"))
      (node (ref "IC16") (pin "12") (pinfunction "GND_12") (pintype "passive"))
      (node (ref "IC16") (pin "14") (pinfunction "GND_14") (pintype "passive"))
      (node (ref "IC16") (pin "15") (pinfunction "GND_15") (pintype "passive"))
      (node (ref "IC16") (pin "9") (pinfunction "GND_9") (pintype "passive"))
      (node (ref "IC3") (pin "12") (pinfunction "GND_12") (pintype "power_in"))
      (node (ref "IC3") (pin "22") (pinfunction "GND_22") (pintype "power_in"))
      (node (ref "IC3") (pin "27") (pinfunction "GND_27") (pintype "power_in"))
      (node (ref "IC3") (pin "3") (pinfunction "GND_3") (pintype "power_in"))
      (node (ref "IC3") (pin "32") (pinfunction "GND_32") (pintype "power_in"))
      (node (ref "IC3") (pin "49") (pinfunction "GND_49") (pintype "power_in"))
      (node (ref "IC3") (pin "50") (pinfunction "GND_50") (pintype "power_in"))
      (node (ref "IC3") (pin "55") (pinfunction "GND_55") (pintype "power_in"))
      (node (ref "IC3") (pin "62") (pinfunction "GND_62") (pintype "power_in"))
      (node (ref "IC3") (pin "65") (pinfunction "EP_65") (pintype "power_in"))
      (node (ref "IC3") (pin "7") (pinfunction "GND_7") (pintype "power_in"))
      (node (ref "IC3") (pin "8") (pinfunction "GND_8") (pintype "power_in"))
      (node (ref "IC4") (pin "1") (pinfunction "GND_1") (pintype "power_in"))
      (node (ref "IC4") (pin "2") (pinfunction "GND_2") (pintype "power_in"))
      (node (ref "IC4") (pin "4") (pinfunction "GND_4") (pintype "power_in"))
      (node (ref "IC4") (pin "5") (pinfunction "GND_5") (pintype "power_in"))
      (node (ref "IC4") (pin "8") (pinfunction "GND_8") (pintype "power_in"))
      (node (ref "J3") (pin "2") (pinfunction "2_2") (pintype "bidirectional"))
      (node (ref "J4") (pin "2") (pinfunction "2_2") (pintype "bidirectional"))
      (node (ref "OSC1") (pin "2") (pinfunction "GND_2") (pintype "power_in"))
      (node (ref "OSC2") (pin "3") (pinfunction "GND_3") (pintype "power_in"))
      (node (ref "R21") (pin "2") (pinfunction "2_2") (pintype "passive"))
      (node (ref "R24") (pin "1") (pinfunction "1_1") (pintype "passive"))
      (node (ref "R25") (pin "2") (pinfunction "2_2") (pintype "passive"))
      (node (ref "R26") (pin "2") (pinfunction "2_2") (pintype "passive"))
      (node (ref "R29") (pin "2") (pinfunction "2_2") (pintype "passive"))
      (node (ref "R30") (pin "2") (pinfunction "2_2") (pintype "passive"))
      (node (ref "R31") (pin "2") (pinfunction "2_2") (pintype "passive"))
      (node (ref "R34") (pin "2") (pinfunction "2_2") (pintype "passive"))
      (node (ref "R36") (pin "2") (pinfunction "2_2") (pintype "passive"))
      (node (ref "R38") (pin "2") (pinfunction "2_2") (pintype "passive"))
      (node (ref "R40") (pin "1") (pinfunction "1_1") (pintype "passive"))
      (node (ref "R46") (pin "1") (pinfunction "1_1") (pintype "passive"))
      (node (ref "R47") (pin "1") (pinfunction "1_1") (pintype "passive"))
      (node (ref "R48") (pin "1") (pinfunction "1_1") (pintype "passive"))
      (node (ref "R52") (pin "2") (pinfunction "2_2") (pintype "passive"))
      (node (ref "TR2") (pin "10") (pinfunction "GND_10") (pintype "power_in"))
      (node (ref "TR2") (pin "3") (pinfunction "GND_3") (pintype "power_in"))
      (node (ref "TR2") (pin "4") (pinfunction "GND_4") (pintype "power_in"))
      (node (ref "TR2") (pin "5") (pinfunction "GND_5") (pintype "power_in"))
      (node (ref "TR2") (pin "9") (pinfunction "GND_9") (pintype "power_in"))
      (node (ref "TR3") (pin "10") (pinfunction "GND_10") (pintype "power_in"))
      (node (ref "TR3") (pin "3") (pinfunction "GND_3") (pintype "power_in"))
      (node (ref "TR3") (pin "4") (pinfunction "GND_4") (pintype "power_in"))
      (node (ref "TR3") (pin "5") (pinfunction "GND_5") (pintype "power_in"))
      (node (ref "TR3") (pin "9") (pinfunction "GND_9") (pintype "power_in"))
      (node (ref "TR4") (pin "10") (pinfunction "GND_10") (pintype "power_in"))
      (node (ref "TR4") (pin "3") (pinfunction "GND_3") (pintype "power_in"))
      (node (ref "TR4") (pin "4") (pinfunction "GND_4") (pintype "power_in"))
      (node (ref "TR4") (pin "5") (pinfunction "GND_5") (pintype "power_in"))
      (node (ref "TR4") (pin "9") (pinfunction "GND_9") (pintype "power_in"))
      (node (ref "TR5") (pin "10") (pinfunction "GND_10") (pintype "power_in"))
      (node (ref "TR5") (pin "3") (pinfunction "GND_3") (pintype "power_in"))
      (node (ref "TR5") (pin "4") (pinfunction "GND_4") (pintype "power_in"))
      (node (ref "TR5") (pin "5") (pinfunction "GND_5") (pintype "power_in"))
      (node (ref "TR5") (pin "9") (pinfunction "GND_9") (pintype "power_in"))
    )
    (net (code "61") (name "Net-(C42-Pad1)") (class "Default")
      (node (ref "C42") (pin "1") (pinfunction "1_1") (pintype "passive"))
      (node (ref "L5") (pin "5") (pinfunction "5_5") (pintype "passive"))
    )
    (net (code "62") (name "Net-(C43-Pad1)") (class "Default")
      (node (ref "C43") (pin "1") (pinfunction "1_1") (pintype "passive"))
      (node (ref "L5") (pin "4") (pinfunction "4_4") (pintype "passive"))
    )
    (net (code "63") (name "Net-(C56-Pad2)") (class "Default")
      (node (ref "C56") (pin "2") (pinfunction "2_2") (pintype "passive"))
      (node (ref "R53") (pin "2") (pinfunction "2_2") (pintype "passive"))
      (node (ref "R54") (pin "2") (pinfunction "2_2") (pintype "passive"))
    )
    (net (code "64") (name "Net-(C58-Pad2)") (class "Default")
      (node (ref "C58") (pin "2") (pinfunction "2_2") (pintype "passive"))
      (node (ref "R55") (pin "1") (pinfunction "1_1") (pintype "passive"))
    )
    (net (code "65") (name "Net-(IC3-CLK2)") (class "Default")
      (node (ref "C45") (pin "1") (pinfunction "1_1") (pintype "passive"))
      (node (ref "IC3") (pin "10") (pinfunction "CLK2_10") (pintype "input"))
    )
    (net (code "66") (name "Net-(IC3-CLK2B)") (class "Default")
      (node (ref "C46") (pin "1") (pinfunction "1_1") (pintype "passive"))
      (node (ref "IC3") (pin "11") (pinfunction "CLK2B_11") (pintype "input"))
    )
    (net (code "67") (name "Net-(IC3-CP)") (class "Default")
      (node (ref "C55") (pin "2") (pinfunction "2_2") (pintype "passive"))
      (node (ref "IC3") (pin "6") (pinfunction "CP_6") (pintype "output"))
      (node (ref "R53") (pin "1") (pinfunction "1_1") (pintype "passive"))
      (node (ref "R55") (pin "2") (pinfunction "2_2") (pintype "passive"))
    )
    (net (code "68") (name "Net-(IC3-CPRSET)") (class "Default")
      (node (ref "IC3") (pin "63") (pinfunction "CPRSET_63") (pintype "input"))
      (node (ref "R46") (pin "2") (pinfunction "2_2") (pintype "passive"))
    )
    (net (code "69") (name "Net-(IC3-RSET)") (class "Default")
      (node (ref "IC3") (pin "61") (pinfunction "RSET_61") (pintype "input"))
      (node (ref "R47") (pin "2") (pinfunction "2_2") (pintype "passive"))
    )
    (net (code "70") (name "Net-(IC3-SDO)") (class "Default")
      (node (ref "IC3") (pin "20") (pinfunction "SDO_20") (pintype "output"))
      (node (ref "R7") (pin "2") (pinfunction "2_2") (pintype "passive"))
    )
    (net (code "71") (name "Net-(IC3-STATUS)") (class "Default")
      (node (ref "IC3") (pin "17") (pinfunction "STATUS_17") (pintype "output"))
      (node (ref "R19") (pin "2") (pinfunction "2_2") (pintype "passive"))
    )
    (net (code "72") (name "Net-(OSC1-OUT)") (class "Default")
      (node (ref "OSC1") (pin "3") (pinfunction "OUT_3") (pintype "output"))
      (node (ref "R51") (pin "1") (pinfunction "1_1") (pintype "passive"))
    )
    (net (code "73") (name "Net-(OSC1-VDD)") (class "Default")
      (node (ref "C10") (pin "1") (pinfunction "1_1") (pintype "passive"))
      (node (ref "C53") (pin "2") (pinfunction "2_2") (pintype "passive"))
      (node (ref "C54") (pin "1") (pinfunction "1_1") (pintype "passive"))
      (node (ref "L8") (pin "2") (pinfunction "2_2") (pintype "passive"))
      (node (ref "OSC1") (pin "4") (pinfunction "VDD_4") (pintype "power_in"))
      (node (ref "OSC2") (pin "6") (pinfunction "VDD_6") (pintype "power_in"))
    )
    (net (code "74") (name "Net-(OSC2-CLK+)") (class "Default")
      (node (ref "OSC2") (pin "4") (pinfunction "CLK+_4") (pintype "output"))
      (node (ref "R72") (pin "1") (pinfunction "1_1") (pintype "passive"))
    )
    (net (code "75") (name "Net-(OSC2-CLK-)") (class "Default")
      (node (ref "OSC2") (pin "5") (pinfunction "CLK-_5") (pintype "output"))
      (node (ref "R73") (pin "1") (pinfunction "1_1") (pintype "passive"))
    )
    (net (code "76") (name "Net-(TR6-P)") (class "Default")
      (node (ref "J10") (pin "2") (pinfunction "2_2") (pintype "bidirectional"))
      (node (ref "R40") (pin "2") (pinfunction "2_2") (pintype "passive"))
      (node (ref "TR6") (pin "4") (pinfunction "P_4") (pintype "passive"))
    )
    (net (code "77") (name "Net-(TR6-PDOT)") (class "Default")
      (node (ref "C48") (pin "1") (pinfunction "1_1") (pintype "passive"))
      (node (ref "TR6") (pin "6") (pinfunction "PDOT_6") (pintype "passive"))
    )
    (net (code "78") (name "P3V3_CLK") (class "Default")
      (node (ref "C105") (pin "2") (pinfunction "2_2") (pintype "passive"))
      (node (ref "C106") (pin "2") (pinfunction "2_2") (pintype "passive"))
      (node (ref "C107") (pin "2") (pinfunction "2_2") (pintype "passive"))
      (node (ref "C108") (pin "2") (pinfunction "2_2") (pintype "passive"))
      (node (ref "C109") (pin "2") (pinfunction "2_2") (pintype "passive"))
      (node (ref "C110") (pin "2") (pinfunction "2_2") (pintype "passive"))
      (node (ref "C50") (pin "1") (pinfunction "1_1") (pintype "passive"))
      (node (ref "C59") (pin "2") (pinfunction "2_2") (pintype "passive"))
      (node (ref "C60") (pin "2") (pinfunction "2_2") (pintype "passive"))
      (node (ref "C61") (pin "2") (pinfunction "2_2") (pintype "passive"))
      (node (ref "C62") (pin "2") (pinfunction "2_2") (pintype "passive"))
      (node (ref "C63") (pin "2") (pinfunction "2_2") (pintype "passive"))
      (node (ref "C64") (pin "2") (pinfunction "2_2") (pintype "passive"))
      (node (ref "C65") (pin "2") (pinfunction "2_2") (pintype "passive"))
      (node (ref "C66") (pin "2") (pinfunction "2_2") (pintype "passive"))
      (node (ref "C67") (pin "2") (pinfunction "2_2") (pintype "passive"))
      (node (ref "C68") (pin "2") (pinfunction "2_2") (pintype "passive"))
      (node (ref "C69") (pin "2") (pinfunction "2_2") (pintype "passive"))
      (node (ref "C70") (pin "2") (pinfunction "2_2") (pintype "passive"))
      (node (ref "C71") (pin "2") (pinfunction "2_2") (pintype "passive"))
      (node (ref "C72") (pin "2") (pinfunction "2_2") (pintype "passive"))
      (node (ref "IC16") (pin "13") (pinfunction "Vdd_13") (pintype "power_in"))
      (node (ref "IC16") (pin "8") (pinfunction "Vdd_8") (pintype "power_in"))
      (node (ref "IC3") (pin "13") (pinfunction "VS_13") (pintype "power_in"))
      (node (ref "IC3") (pin "23") (pinfunction "VS_23") (pintype "power_in"))
      (node (ref "IC3") (pin "26") (pinfunction "VS_26") (pintype "power_in"))
      (node (ref "IC3") (pin "30") (pinfunction "VS_30") (pintype "power_in"))
      (node (ref "IC3") (pin "31") (pinfunction "VS_31") (pintype "power_in"))
      (node (ref "IC3") (pin "33") (pinfunction "VS_33") (pintype "power_in"))
      (node (ref "IC3") (pin "36") (pinfunction "VS_36") (pintype "power_in"))
      (node (ref "IC3") (pin "37") (pinfunction "VS_37") (pintype "power_in"))
      (node (ref "IC3") (pin "4") (pinfunction "VS_4") (pintype "power_in"))
      (node (ref "IC3") (pin "40") (pinfunction "VS_40") (pintype "power_in"))
      (node (ref "IC3") (pin "41") (pinfunction "VS_41") (pintype "power_in"))
      (node (ref "IC3") (pin "44") (pinfunction "VS_44") (pintype "power_in"))
      (node (ref "IC3") (pin "45") (pinfunction "VS_45") (pintype "power_in"))
      (node (ref "IC3") (pin "48") (pinfunction "VS_48") (pintype "power_in"))
      (node (ref "IC3") (pin "5") (pinfunction "VCP_5") (pintype "power_in"))
      (node (ref "IC3") (pin "51") (pinfunction "VS_51") (pintype "power_in"))
      (node (ref "IC3") (pin "52") (pinfunction "VS_52") (pintype "power_in"))
      (node (ref "IC3") (pin "56") (pinfunction "VS_56") (pintype "power_in"))
      (node (ref "IC3") (pin "59") (pinfunction "VS_59") (pintype "power_in"))
      (node (ref "IC3") (pin "60") (pinfunction "VS_60") (pintype "power_in"))
      (node (ref "IC3") (pin "64") (pinfunction "VS_64") (pintype "power_in"))
      (node (ref "IC3") (pin "9") (pinfunction "VS_9") (pintype "power_in"))
      (node (ref "L8") (pin "1") (pinfunction "1_1") (pintype "passive"))
      (node (ref "R49") (pin "2") (pinfunction "2_2") (pintype "passive"))
      (node (ref "R50") (pin "2") (pinfunction "2_2") (pintype "passive"))
    )
    (net (code "79") (name "unconnected-(IC3-OUT5-Pad43)") (class "Default")
      (node (ref "IC3") (pin "43") (pinfunction "OUT5_43") (pintype "output"))
    )
    (net (code "80") (name "unconnected-(IC3-OUT5B-Pad42)") (class "Default")
      (node (ref "IC3") (pin "42") (pinfunction "OUT5B_42") (pintype "output"))
    )
    (net (code "81") (name "unconnected-(IC3-OUT6-Pad39)") (class "Default")
      (node (ref "IC3") (pin "39") (pinfunction "OUT6_39") (pintype "output"))
    )
    (net (code "82") (name "unconnected-(IC3-OUT6B-Pad38)") (class "Default")
      (node (ref "IC3") (pin "38") (pinfunction "OUT6B_38") (pintype "output"))
    )
    (net (code "83") (name "unconnected-(IC16-nc-Pad7)") (class "Default")
      (node (ref "IC16") (pin "7") (pinfunction "nc_7") (pintype "passive"))
    )
    (net (code "84") (name "unconnected-(IC16-nc-Pad16)") (class "Default")
      (node (ref "IC16") (pin "16") (pinfunction "nc_16") (pintype "passive"))
    )
    (net (code "85") (name "unconnected-(IC16-reserved-Pad5)") (class "Default")
      (node (ref "IC16") (pin "5") (pinfunction "reserved_5") (pintype "passive"))
    )
    (net (code "86") (name "unconnected-(TR2-OPEN-Pad2)") (class "Default")
      (node (ref "TR2") (pin "2") (pinfunction "OPEN_2") (pintype "passive"))
    )
    (net (code "87") (name "unconnected-(TR2-OPEN-Pad7)") (class "Default")
      (node (ref "TR2") (pin "7") (pinfunction "OPEN_7") (pintype "passive"))
    )
    (net (code "88") (name "unconnected-(TR3-OPEN-Pad2)") (class "Default")
      (node (ref "TR3") (pin "2") (pinfunction "OPEN_2") (pintype "passive"))
    )
    (net (code "89") (name "unconnected-(TR3-OPEN-Pad7)") (class "Default")
      (node (ref "TR3") (pin "7") (pinfunction "OPEN_7") (pintype "passive"))
    )
    (net (code "90") (name "unconnected-(TR4-OPEN-Pad2)") (class "Default")
      (node (ref "TR4") (pin "2") (pinfunction "OPEN_2") (pintype "passive"))
    )
    (net (code "91") (name "unconnected-(TR4-OPEN-Pad7)") (class "Default")
      (node (ref "TR4") (pin "7") (pinfunction "OPEN_7") (pintype "passive"))
    )
    (net (code "92") (name "unconnected-(TR5-OPEN-Pad2)") (class "Default")
      (node (ref "TR5") (pin "2") (pinfunction "OPEN_2") (pintype "passive"))
    )
    (net (code "93") (name "unconnected-(TR5-OPEN-Pad7)") (class "Default")
      (node (ref "TR5") (pin "7") (pinfunction "OPEN_7") (pintype "passive"))
    )
    (net (code "94") (name "unconnected-(TR6-NU-Pad2)") (class "Default")
      (node (ref "TR6") (pin "2") (pinfunction "NU_2") (pintype "passive"))
    )
  )
)
